# zeropi.net
KiCad netlist of a schematic drawn in EAGLE
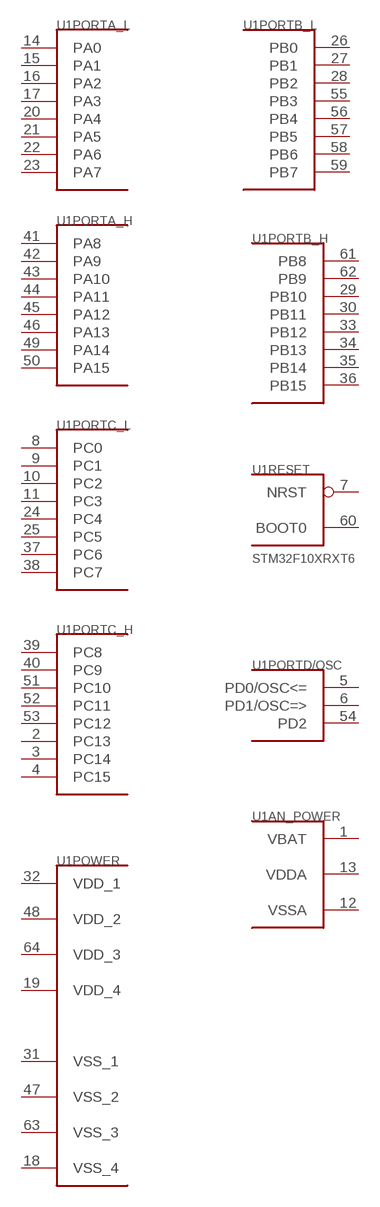
[diagram p0: schematic, sheet 1]
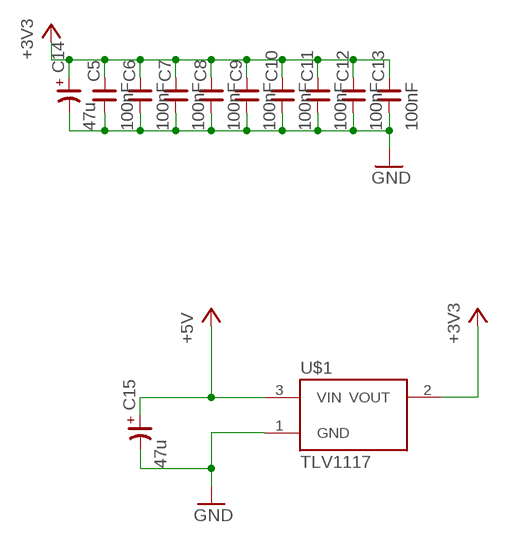
[diagram p1: schematic, sheet 2]
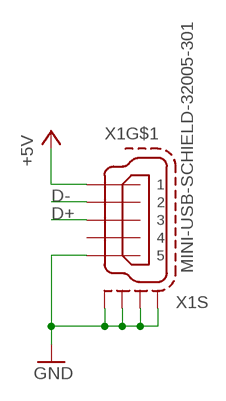
[diagram p2: schematic, sheet 3]

(export (version "E")
  (design (tool "Eeschema 10.0.6"))
  (components
    (comp (ref "C5")
      (value "100nF")
      (footprint "eagle-import:0805")
      (libsource (lib "eagle-import") (part "CNP-0805"))
    )
    (comp (ref "C6")
      (value "100nF")
      (footprint "eagle-import:0805")
      (libsource (lib "eagle-import") (part "CNP-0805"))
    )
    (comp (ref "C7")
      (value "100nF")
      (footprint "eagle-import:0805")
      (libsource (lib "eagle-import") (part "CNP-0805"))
    )
    (comp (ref "C8")
      (value "100nF")
      (footprint "eagle-import:0805")
      (libsource (lib "eagle-import") (part "CNP-0805"))
    )
    (comp (ref "C9")
      (value "100nF")
      (footprint "eagle-import:0805")
      (libsource (lib "eagle-import") (part "CNP-0805"))
    )
    (comp (ref "C10")
      (value "100nF")
      (footprint "eagle-import:0805")
      (libsource (lib "eagle-import") (part "CNP-0805"))
    )
    (comp (ref "C11")
      (value "100nF")
      (footprint "eagle-import:0805")
      (libsource (lib "eagle-import") (part "CNP-0805"))
    )
    (comp (ref "C12")
      (value "100nF")
      (footprint "eagle-import:0805")
      (libsource (lib "eagle-import") (part "CNP-0805"))
    )
    (comp (ref "C13")
      (value "100nF")
      (footprint "eagle-import:0805")
      (libsource (lib "eagle-import") (part "CNP-0805"))
    )
    (comp (ref "C14")
      (value "47u")
      (footprint "eagle-import:153CLV-1012")
      (libsource (lib "eagle-import") (part "CP-153CLV-1012"))
    )
    (comp (ref "C15")
      (value "47u")
      (footprint "eagle-import:153CLV-1012")
      (libsource (lib "eagle-import") (part "CP-153CLV-1012"))
    )
    (comp (ref "U$1")
      (value "TLV1117")
      (footprint "eagle-import:SOT223")
      (libsource (lib "eagle-import") (part "TLV1117"))
    )
    (comp (ref "X1")
      (value "MINI-USB-SCHIELD-32005-301")
      (footprint "eagle-import:32005-301")
      (libsource (lib "eagle-import") (part "MINI-USB-SCHIELD-32005-301"))
    )
    (comp (ref "U1")
      (value "STM32F10XRXT6")
      (footprint "eagle-import:TQFP64")
      (libsource (lib "eagle-import") (part "STM32F10XRXT6"))
    )
  )
  (nets
    (net (code "1") (name "+3V3") (class "Default")
      (node (ref "C10") (pin "2") (pinfunction "2_2") (pintype "passive"))
      (node (ref "C11") (pin "2") (pinfunction "2_2") (pintype "passive"))
      (node (ref "C12") (pin "2") (pinfunction "2_2") (pintype "passive"))
      (node (ref "C13") (pin "2") (pinfunction "2_2") (pintype "passive"))
      (node (ref "C14") (pin "+") (pinfunction "+_+") (pintype "passive"))
      (node (ref "C5") (pin "2") (pinfunction "2_2") (pintype "passive"))
      (node (ref "C6") (pin "2") (pinfunction "2_2") (pintype "passive"))
      (node (ref "C7") (pin "2") (pinfunction "2_2") (pintype "passive"))
      (node (ref "C8") (pin "2") (pinfunction "2_2") (pintype "passive"))
      (node (ref "C9") (pin "2") (pinfunction "2_2") (pintype "passive"))
      (node (ref "U$1") (pin "2") (pinfunction "VOUT_2") (pintype "power_in"))
      (node (ref "U$1") (pin "4") (pinfunction "VOUT2_4") (pintype "power_in"))
    )
    (net (code "2") (name "+5V") (class "Default")
      (node (ref "C15") (pin "+") (pinfunction "+_+") (pintype "passive"))
      (node (ref "U$1") (pin "3") (pinfunction "VIN_3") (pintype "power_in"))
      (node (ref "X1") (pin "1") (pinfunction "1_1") (pintype "passive"))
    )
    (net (code "3") (name "D+") (class "Default")
      (node (ref "X1") (pin "3") (pinfunction "3_3") (pintype "passive"))
    )
    (net (code "4") (name "D-") (class "Default")
      (node (ref "X1") (pin "2") (pinfunction "2_2") (pintype "passive"))
    )
    (net (code "5") (name "GND") (class "Default")
      (node (ref "C10") (pin "1") (pinfunction "1_1") (pintype "passive"))
      (node (ref "C11") (pin "1") (pinfunction "1_1") (pintype "passive"))
      (node (ref "C12") (pin "1") (pinfunction "1_1") (pintype "passive"))
      (node (ref "C13") (pin "1") (pinfunction "1_1") (pintype "passive"))
      (node (ref "C14") (pin "-") (pinfunction "-_-") (pintype "passive"))
      (node (ref "C15") (pin "-") (pinfunction "-_-") (pintype "passive"))
      (node (ref "C5") (pin "1") (pinfunction "1_1") (pintype "passive"))
      (node (ref "C6") (pin "1") (pinfunction "1_1") (pintype "passive"))
      (node (ref "C7") (pin "1") (pinfunction "1_1") (pintype "passive"))
      (node (ref "C8") (pin "1") (pinfunction "1_1") (pintype "passive"))
      (node (ref "C9") (pin "1") (pinfunction "1_1") (pintype "passive"))
      (node (ref "U$1") (pin "1") (pinfunction "GND_1") (pintype "power_in"))
      (node (ref "X1") (pin "5") (pinfunction "5_5") (pintype "passive"))
      (node (ref "X1") (pin "M1") (pinfunction "S1_M1") (pintype "passive"))
      (node (ref "X1") (pin "M2") (pinfunction "S2_M2") (pintype "passive"))
      (node (ref "X1") (pin "M3") (pinfunction "S3_M3") (pintype "passive"))
      (node (ref "X1") (pin "M4") (pinfunction "S4_M4") (pintype "passive"))
    )
    (net (code "6") (name "VBAT") (class "Default")
      (node (ref "U1") (pin "1") (pinfunction "VBAT_1") (pintype "power_in"))
    )
    (net (code "7") (name "VDDA") (class "Default")
      (node (ref "U1") (pin "13") (pinfunction "VDDA_13") (pintype "power_in"))
    )
    (net (code "8") (name "VDD_1") (class "Default")
      (node (ref "U1") (pin "32") (pinfunction "VDD_1_32") (pintype "power_in"))
    )
    (net (code "9") (name "VDD_2") (class "Default")
      (node (ref "U1") (pin "48") (pinfunction "VDD_2_48") (pintype "power_in"))
    )
    (net (code "10") (name "VDD_3") (class "Default")
      (node (ref "U1") (pin "64") (pinfunction "VDD_3_64") (pintype "power_in"))
    )
    (net (code "11") (name "VDD_4") (class "Default")
      (node (ref "U1") (pin "19") (pinfunction "VDD_4_19") (pintype "power_in"))
    )
    (net (code "12") (name "VSSA") (class "Default")
      (node (ref "U1") (pin "12") (pinfunction "VSSA_12") (pintype "power_in"))
    )
    (net (code "13") (name "VSS_1") (class "Default")
      (node (ref "U1") (pin "31") (pinfunction "VSS_1_31") (pintype "power_in"))
    )
    (net (code "14") (name "VSS_2") (class "Default")
      (node (ref "U1") (pin "47") (pinfunction "VSS_2_47") (pintype "power_in"))
    )
    (net (code "15") (name "VSS_3") (class "Default")
      (node (ref "U1") (pin "63") (pinfunction "VSS_3_63") (pintype "power_in"))
    )
    (net (code "16") (name "VSS_4") (class "Default")
      (node (ref "U1") (pin "18") (pinfunction "VSS_4_18") (pintype "power_in"))
    )
    (net (code "17") (name "unconnected-(U1B-PA8-Pad41)") (class "Default")
      (node (ref "U1") (pin "41") (pinfunction "PA8_41") (pintype "bidirectional"))
    )
    (net (code "18") (name "unconnected-(U1B-PA9-Pad42)") (class "Default")
      (node (ref "U1") (pin "42") (pinfunction "PA9_42") (pintype "bidirectional"))
    )
    (net (code "19") (name "unconnected-(U1B-PA10-Pad43)") (class "Default")
      (node (ref "U1") (pin "43") (pinfunction "PA10_43") (pintype "bidirectional"))
    )
    (net (code "20") (name "unconnected-(U1B-PA11-Pad44)") (class "Default")
      (node (ref "U1") (pin "44") (pinfunction "PA11_44") (pintype "bidirectional"))
    )
    (net (code "21") (name "unconnected-(U1B-PA12-Pad45)") (class "Default")
      (node (ref "U1") (pin "45") (pinfunction "PA12_45") (pintype "bidirectional"))
    )
    (net (code "22") (name "unconnected-(U1B-PA13-Pad46)") (class "Default")
      (node (ref "U1") (pin "46") (pinfunction "PA13_46") (pintype "bidirectional"))
    )
    (net (code "23") (name "unconnected-(U1B-PA14-Pad49)") (class "Default")
      (node (ref "U1") (pin "49") (pinfunction "PA14_49") (pintype "bidirectional"))
    )
    (net (code "24") (name "unconnected-(U1B-PA15-Pad50)") (class "Default")
      (node (ref "U1") (pin "50") (pinfunction "PA15_50") (pintype "bidirectional"))
    )
    (net (code "25") (name "unconnected-(U1C-PA0-Pad14)") (class "Default")
      (node (ref "U1") (pin "14") (pinfunction "PA0_14") (pintype "bidirectional"))
    )
    (net (code "26") (name "unconnected-(U1C-PA1-Pad15)") (class "Default")
      (node (ref "U1") (pin "15") (pinfunction "PA1_15") (pintype "bidirectional"))
    )
    (net (code "27") (name "unconnected-(U1C-PA2-Pad16)") (class "Default")
      (node (ref "U1") (pin "16") (pinfunction "PA2_16") (pintype "bidirectional"))
    )
    (net (code "28") (name "unconnected-(U1C-PA3-Pad17)") (class "Default")
      (node (ref "U1") (pin "17") (pinfunction "PA3_17") (pintype "bidirectional"))
    )
    (net (code "29") (name "unconnected-(U1C-PA4-Pad20)") (class "Default")
      (node (ref "U1") (pin "20") (pinfunction "PA4_20") (pintype "bidirectional"))
    )
    (net (code "30") (name "unconnected-(U1C-PA5-Pad21)") (class "Default")
      (node (ref "U1") (pin "21") (pinfunction "PA5_21") (pintype "bidirectional"))
    )
    (net (code "31") (name "unconnected-(U1C-PA6-Pad22)") (class "Default")
      (node (ref "U1") (pin "22") (pinfunction "PA6_22") (pintype "bidirectional"))
    )
    (net (code "32") (name "unconnected-(U1C-PA7-Pad23)") (class "Default")
      (node (ref "U1") (pin "23") (pinfunction "PA7_23") (pintype "bidirectional"))
    )
    (net (code "33") (name "unconnected-(U1D-PB8-Pad61)") (class "Default")
      (node (ref "U1") (pin "61") (pinfunction "PB8_61") (pintype "bidirectional"))
    )
    (net (code "34") (name "unconnected-(U1D-PB9-Pad62)") (class "Default")
      (node (ref "U1") (pin "62") (pinfunction "PB9_62") (pintype "bidirectional"))
    )
    (net (code "35") (name "unconnected-(U1D-PB10-Pad29)") (class "Default")
      (node (ref "U1") (pin "29") (pinfunction "PB10_29") (pintype "bidirectional"))
    )
    (net (code "36") (name "unconnected-(U1D-PB11-Pad30)") (class "Default")
      (node (ref "U1") (pin "30") (pinfunction "PB11_30") (pintype "bidirectional"))
    )
    (net (code "37") (name "unconnected-(U1D-PB12-Pad33)") (class "Default")
      (node (ref "U1") (pin "33") (pinfunction "PB12_33") (pintype "bidirectional"))
    )
    (net (code "38") (name "unconnected-(U1D-PB13-Pad34)") (class "Default")
      (node (ref "U1") (pin "34") (pinfunction "PB13_34") (pintype "bidirectional"))
    )
    (net (code "39") (name "unconnected-(U1D-PB14-Pad35)") (class "Default")
      (node (ref "U1") (pin "35") (pinfunction "PB14_35") (pintype "bidirectional"))
    )
    (net (code "40") (name "unconnected-(U1D-PB15-Pad36)") (class "Default")
      (node (ref "U1") (pin "36") (pinfunction "PB15_36") (pintype "bidirectional"))
    )
    (net (code "41") (name "unconnected-(U1E-PB0-Pad26)") (class "Default")
      (node (ref "U1") (pin "26") (pinfunction "PB0_26") (pintype "bidirectional"))
    )
    (net (code "42") (name "unconnected-(U1E-PB1-Pad27)") (class "Default")
      (node (ref "U1") (pin "27") (pinfunction "PB1_27") (pintype "bidirectional"))
    )
    (net (code "43") (name "unconnected-(U1E-PB2-Pad28)") (class "Default")
      (node (ref "U1") (pin "28") (pinfunction "PB2_28") (pintype "bidirectional"))
    )
    (net (code "44") (name "unconnected-(U1E-PB3-Pad55)") (class "Default")
      (node (ref "U1") (pin "55") (pinfunction "PB3_55") (pintype "bidirectional"))
    )
    (net (code "45") (name "unconnected-(U1E-PB4-Pad56)") (class "Default")
      (node (ref "U1") (pin "56") (pinfunction "PB4_56") (pintype "bidirectional"))
    )
    (net (code "46") (name "unconnected-(U1E-PB5-Pad57)") (class "Default")
      (node (ref "U1") (pin "57") (pinfunction "PB5_57") (pintype "bidirectional"))
    )
    (net (code "47") (name "unconnected-(U1E-PB6-Pad58)") (class "Default")
      (node (ref "U1") (pin "58") (pinfunction "PB6_58") (pintype "bidirectional"))
    )
    (net (code "48") (name "unconnected-(U1E-PB7-Pad59)") (class "Default")
      (node (ref "U1") (pin "59") (pinfunction "PB7_59") (pintype "bidirectional"))
    )
    (net (code "49") (name "unconnected-(U1F-PC8-Pad39)") (class "Default")
      (node (ref "U1") (pin "39") (pinfunction "PC8_39") (pintype "bidirectional"))
    )
    (net (code "50") (name "unconnected-(U1F-PC9-Pad40)") (class "Default")
      (node (ref "U1") (pin "40") (pinfunction "PC9_40") (pintype "bidirectional"))
    )
    (net (code "51") (name "unconnected-(U1F-PC10-Pad51)") (class "Default")
      (node (ref "U1") (pin "51") (pinfunction "PC10_51") (pintype "bidirectional"))
    )
    (net (code "52") (name "unconnected-(U1F-PC11-Pad52)") (class "Default")
      (node (ref "U1") (pin "52") (pinfunction "PC11_52") (pintype "bidirectional"))
    )
    (net (code "53") (name "unconnected-(U1F-PC12-Pad53)") (class "Default")
      (node (ref "U1") (pin "53") (pinfunction "PC12_53") (pintype "bidirectional"))
    )
    (net (code "54") (name "unconnected-(U1F-PC13-Pad2)") (class "Default")
      (node (ref "U1") (pin "2") (pinfunction "PC13_2") (pintype "bidirectional"))
    )
    (net (code "55") (name "unconnected-(U1F-PC14-Pad3)") (class "Default")
      (node (ref "U1") (pin "3") (pinfunction "PC14_3") (pintype "bidirectional"))
    )
    (net (code "56") (name "unconnected-(U1F-PC15-Pad4)") (class "Default")
      (node (ref "U1") (pin "4") (pinfunction "PC15_4") (pintype "bidirectional"))
    )
    (net (code "57") (name "unconnected-(U1G-PC0-Pad8)") (class "Default")
      (node (ref "U1") (pin "8") (pinfunction "PC0_8") (pintype "bidirectional"))
    )
    (net (code "58") (name "unconnected-(U1G-PC1-Pad9)") (class "Default")
      (node (ref "U1") (pin "9") (pinfunction "PC1_9") (pintype "bidirectional"))
    )
    (net (code "59") (name "unconnected-(U1G-PC2-Pad10)") (class "Default")
      (node (ref "U1") (pin "10") (pinfunction "PC2_10") (pintype "bidirectional"))
    )
    (net (code "60") (name "unconnected-(U1G-PC3-Pad11)") (class "Default")
      (node (ref "U1") (pin "11") (pinfunction "PC3_11") (pintype "bidirectional"))
    )
    (net (code "61") (name "unconnected-(U1G-PC4-Pad24)") (class "Default")
      (node (ref "U1") (pin "24") (pinfunction "PC4_24") (pintype "bidirectional"))
    )
    (net (code "62") (name "unconnected-(U1G-PC5-Pad25)") (class "Default")
      (node (ref "U1") (pin "25") (pinfunction "PC5_25") (pintype "bidirectional"))
    )
    (net (code "63") (name "unconnected-(U1G-PC6-Pad37)") (class "Default")
      (node (ref "U1") (pin "37") (pinfunction "PC6_37") (pintype "bidirectional"))
    )
    (net (code "64") (name "unconnected-(U1G-PC7-Pad38)") (class "Default")
      (node (ref "U1") (pin "38") (pinfunction "PC7_38") (pintype "bidirectional"))
    )
    (net (code "65") (name "unconnected-(U1H-PD0{slash}OSC<=-Pad5)") (class "Default")
      (node (ref "U1") (pin "5") (pinfunction "PD0/OSC<=_5") (pintype "bidirectional"))
    )
    (net (code "66") (name "unconnected-(U1H-PD1{slash}OSC=>-Pad6)") (class "Default")
      (node (ref "U1") (pin "6") (pinfunction "PD1/OSC=>_6") (pintype "bidirectional"))
    )
    (net (code "67") (name "unconnected-(U1H-PD2-Pad54)") (class "Default")
      (node (ref "U1") (pin "54") (pinfunction "PD2_54") (pintype "bidirectional"))
    )
    (net (code "68") (name "unconnected-(U1J-BOOT0-Pad60)") (class "Default")
      (node (ref "U1") (pin "60") (pinfunction "BOOT0_60") (pintype "input"))
    )
    (net (code "69") (name "unconnected-(U1J-NRST-Pad7)") (class "Default")
      (node (ref "U1") (pin "7") (pinfunction "NRST_7") (pintype "input"))
    )
    (net (code "70") (name "unconnected-(X1-Pad4)") (class "Default")
      (node (ref "X1") (pin "4") (pinfunction "4_4") (pintype "passive"))
    )
  )
)
